# proto_shield_MEGA-REV3.net
KiCad netlist of a schematic drawn in EAGLE
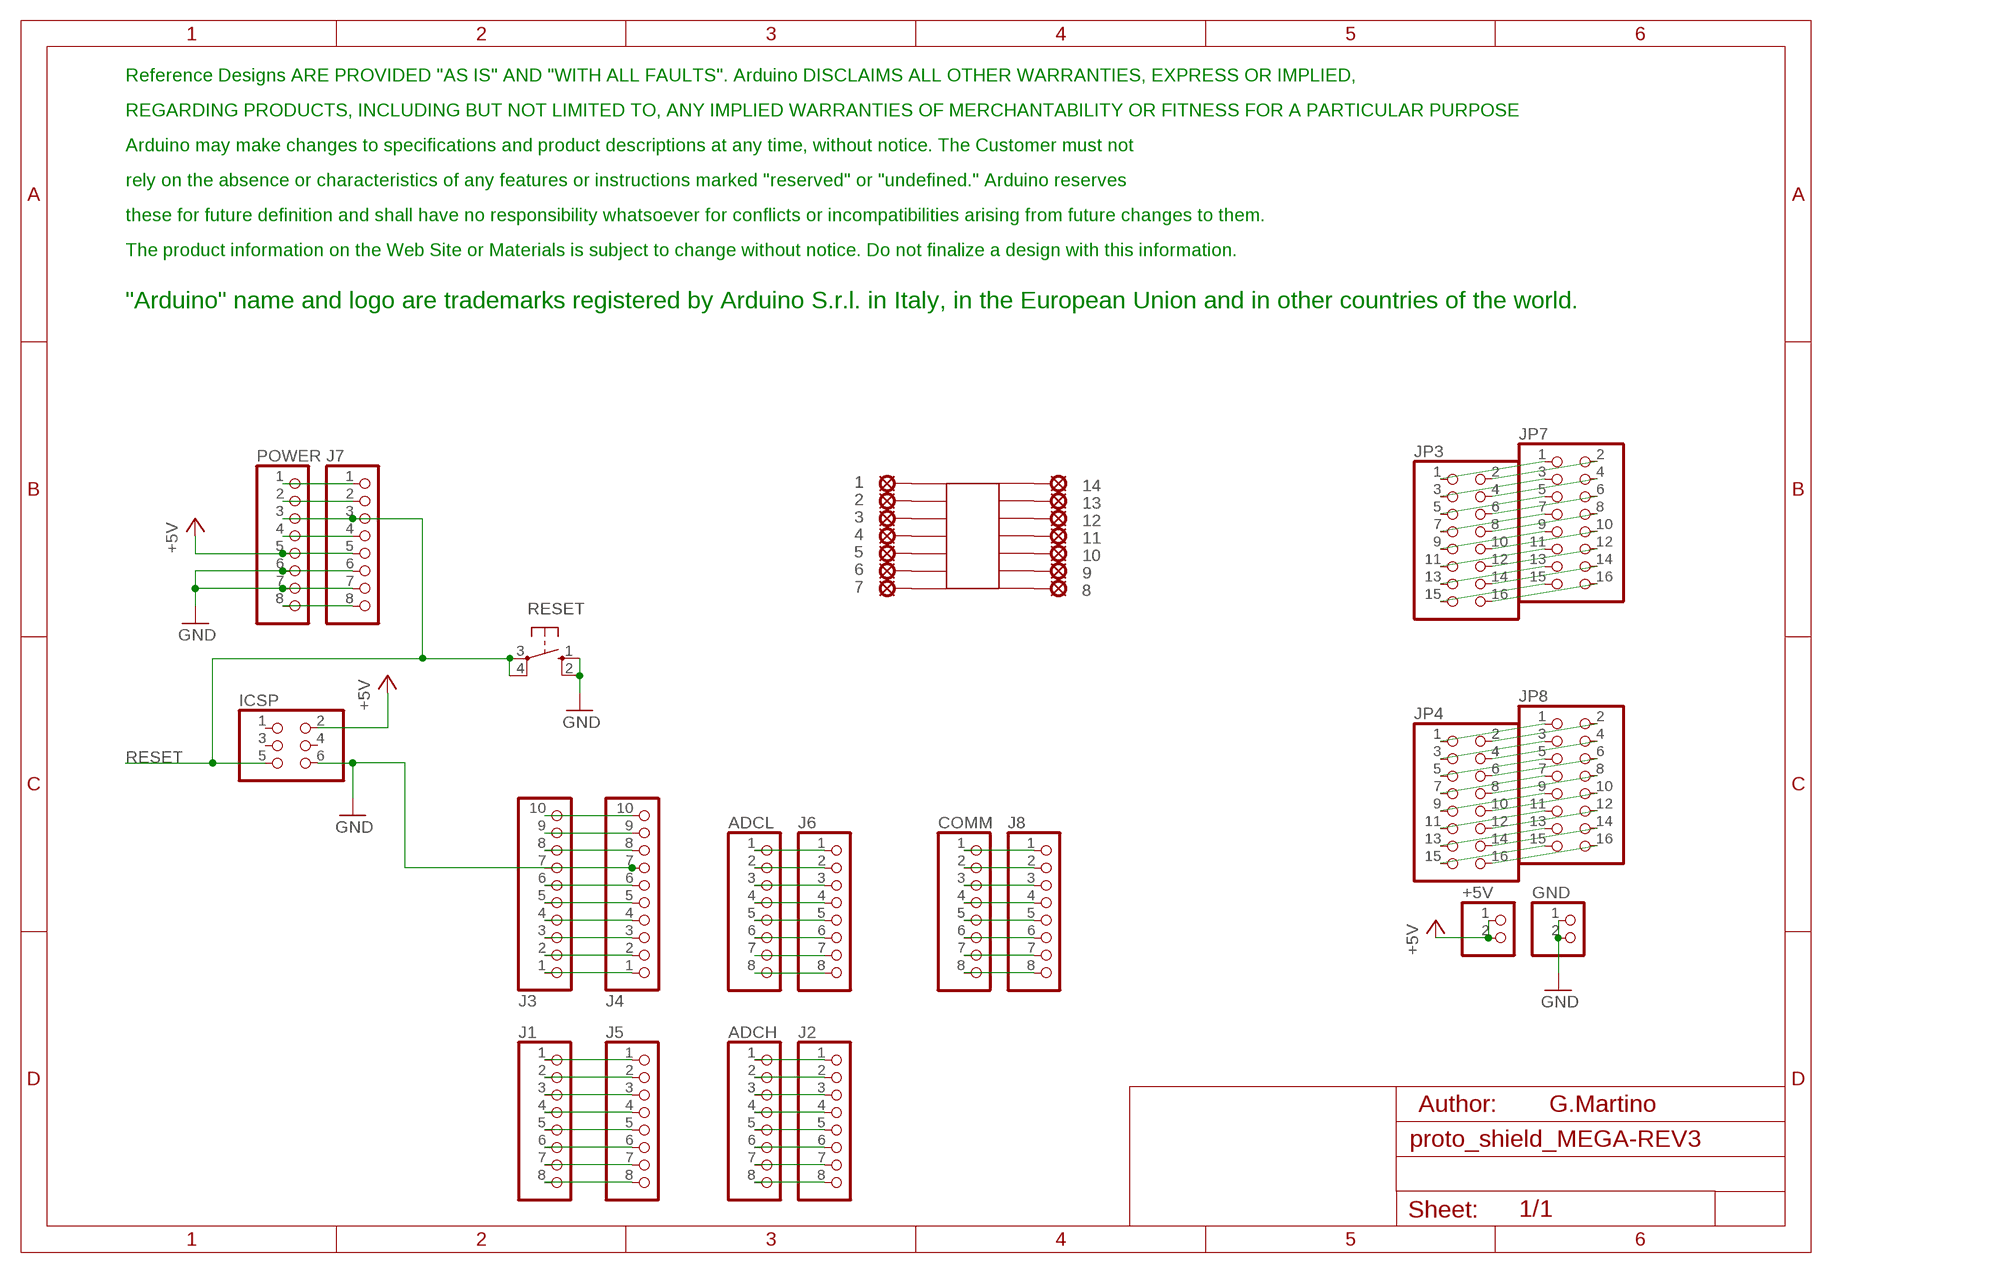
[diagram p0: schematic, sheet 1]

(export (version "E")
  (design (tool "Eeschema 10.0.6"))
  (components
    (comp (ref "+5V")
      (value "PINHD-1X2")
      (footprint "eagle-import:1X02")
      (libsource (lib "eagle-import") (part "PINHD-1X2"))
    )
    (comp (ref "1")
      (value "LSP10")
      (footprint "eagle-import:LSP10")
      (libsource (lib "eagle-import") (part "LSP10"))
    )
    (comp (ref "2")
      (value "LSP10")
      (footprint "eagle-import:LSP10")
      (libsource (lib "eagle-import") (part "LSP10"))
    )
    (comp (ref "3")
      (value "LSP10")
      (footprint "eagle-import:LSP10")
      (libsource (lib "eagle-import") (part "LSP10"))
    )
    (comp (ref "4")
      (value "LSP10")
      (footprint "eagle-import:LSP10")
      (libsource (lib "eagle-import") (part "LSP10"))
    )
    (comp (ref "5")
      (value "LSP10")
      (footprint "eagle-import:LSP10")
      (libsource (lib "eagle-import") (part "LSP10"))
    )
    (comp (ref "6")
      (value "LSP10")
      (footprint "eagle-import:LSP10")
      (libsource (lib "eagle-import") (part "LSP10"))
    )
    (comp (ref "7")
      (value "LSP10")
      (footprint "eagle-import:LSP10")
      (libsource (lib "eagle-import") (part "LSP10"))
    )
    (comp (ref "8")
      (value "LSP10")
      (footprint "eagle-import:LSP10")
      (libsource (lib "eagle-import") (part "LSP10"))
    )
    (comp (ref "9")
      (value "LSP10")
      (footprint "eagle-import:LSP10")
      (libsource (lib "eagle-import") (part "LSP10"))
    )
    (comp (ref "10")
      (value "LSP10")
      (footprint "eagle-import:LSP10")
      (libsource (lib "eagle-import") (part "LSP10"))
    )
    (comp (ref "11")
      (value "LSP10")
      (footprint "eagle-import:LSP10")
      (libsource (lib "eagle-import") (part "LSP10"))
    )
    (comp (ref "12")
      (value "LSP10")
      (footprint "eagle-import:LSP10")
      (libsource (lib "eagle-import") (part "LSP10"))
    )
    (comp (ref "13")
      (value "LSP10")
      (footprint "eagle-import:LSP10")
      (libsource (lib "eagle-import") (part "LSP10"))
    )
    (comp (ref "14")
      (value "LSP10")
      (footprint "eagle-import:LSP10")
      (libsource (lib "eagle-import") (part "LSP10"))
    )
    (comp (ref "ADCH")
      (value "PINHD-1X8TH")
      (footprint "eagle-import:1X08-TH")
      (libsource (lib "eagle-import") (part "PINHD-1X8TH"))
    )
    (comp (ref "ADCL")
      (value "PINHD-1X8TH")
      (footprint "eagle-import:1X08-TH")
      (libsource (lib "eagle-import") (part "PINHD-1X8TH"))
    )
    (comp (ref "COMM")
      (value "PINHD-1X8TH")
      (footprint "eagle-import:1X08-TH")
      (libsource (lib "eagle-import") (part "PINHD-1X8TH"))
    )
    (comp (ref "GND")
      (value "PINHD-1X2")
      (footprint "eagle-import:1X02")
      (libsource (lib "eagle-import") (part "PINHD-1X2"))
    )
    (comp (ref "IC2")
      (value "SMD-14")
      (footprint "eagle-import:SO-14NMW")
      (libsource (lib "eagle-import") (part "SMD-14"))
    )
    (comp (ref "ICSP")
      (value "PINHD-2X3")
      (footprint "eagle-import:2X03")
      (libsource (lib "eagle-import") (part "PINHD-2X3"))
    )
    (comp (ref "J1")
      (value "PINHD-1X8TH")
      (footprint "eagle-import:1X08-TH")
      (libsource (lib "eagle-import") (part "PINHD-1X8TH"))
    )
    (comp (ref "J2")
      (value "PINHD-1X8TH")
      (footprint "eagle-import:1X08-TH")
      (libsource (lib "eagle-import") (part "PINHD-1X8TH"))
    )
    (comp (ref "J3")
      (value "PINHD-1X10TH")
      (footprint "eagle-import:1X10-TH")
      (libsource (lib "eagle-import") (part "PINHD-1X10TH"))
    )
    (comp (ref "J4")
      (value "PINHD-1X10TH")
      (footprint "eagle-import:1X10-TH")
      (libsource (lib "eagle-import") (part "PINHD-1X10TH"))
    )
    (comp (ref "J5")
      (value "PINHD-1X8TH")
      (footprint "eagle-import:1X08-TH")
      (libsource (lib "eagle-import") (part "PINHD-1X8TH"))
    )
    (comp (ref "J6")
      (value "PINHD-1X8TH")
      (footprint "eagle-import:1X08-TH")
      (libsource (lib "eagle-import") (part "PINHD-1X8TH"))
    )
    (comp (ref "J7")
      (value "PINHD-1X8TH")
      (footprint "eagle-import:1X08-TH")
      (libsource (lib "eagle-import") (part "PINHD-1X8TH"))
    )
    (comp (ref "J8")
      (value "PINHD-1X8TH")
      (footprint "eagle-import:1X08-TH")
      (libsource (lib "eagle-import") (part "PINHD-1X8TH"))
    )
    (comp (ref "JP3")
      (value "PINHD-2X8")
      (footprint "eagle-import:2X08")
      (libsource (lib "eagle-import") (part "PINHD-2X8"))
    )
    (comp (ref "JP4")
      (value "PINHD-2X8")
      (footprint "eagle-import:2X08")
      (libsource (lib "eagle-import") (part "PINHD-2X8"))
    )
    (comp (ref "JP7")
      (value "PINHD-2X8")
      (footprint "eagle-import:2X08")
      (libsource (lib "eagle-import") (part "PINHD-2X8"))
    )
    (comp (ref "JP8")
      (value "PINHD-2X8")
      (footprint "eagle-import:2X08")
      (libsource (lib "eagle-import") (part "PINHD-2X8"))
    )
    (comp (ref "POWER")
      (value "PINHD-1X8TH")
      (footprint "eagle-import:1X08-TH")
      (libsource (lib "eagle-import") (part "PINHD-1X8TH"))
    )
    (comp (ref "RESET")
      (value "10-XX")
      (footprint "eagle-import:B3F-10XX")
      (libsource (lib "eagle-import") (part "10-XX"))
    )
    (comp (ref "U$1")
      (value "DISCLAIMER_MINI")
      (footprint "eagle-import:DISCLAIMER")
      (libsource (lib "eagle-import") (part "DISCLAIMER_MINI"))
    )
  )
  (nets
    (net (code "1") (name "+5V") (class "Default")
      (node (ref "+5V") (pin "1") (pinfunction "1_1") (pintype "passive"))
      (node (ref "+5V") (pin "2") (pinfunction "2_2") (pintype "passive"))
      (node (ref "ICSP") (pin "2") (pinfunction "2_2") (pintype "passive"))
      (node (ref "J7") (pin "5") (pinfunction "5_5") (pintype "passive"))
      (node (ref "POWER") (pin "5") (pinfunction "5_5") (pintype "passive"))
    )
    (net (code "2") (name "/RESET") (class "Default")
      (node (ref "ICSP") (pin "5") (pinfunction "5_5") (pintype "passive"))
      (node (ref "J7") (pin "3") (pinfunction "3_3") (pintype "passive"))
      (node (ref "POWER") (pin "3") (pinfunction "3_3") (pintype "passive"))
      (node (ref "RESET") (pin "3") (pinfunction "P_3") (pintype "passive"))
      (node (ref "RESET") (pin "4") (pinfunction "P1_4") (pintype "passive"))
    )
    (net (code "3") (name "GND") (class "Default")
      (node (ref "GND") (pin "1") (pinfunction "1_1") (pintype "passive"))
      (node (ref "GND") (pin "2") (pinfunction "2_2") (pintype "passive"))
      (node (ref "ICSP") (pin "6") (pinfunction "6_6") (pintype "passive"))
      (node (ref "J3") (pin "7") (pinfunction "7_7") (pintype "passive"))
      (node (ref "J4") (pin "7") (pinfunction "7_7") (pintype "passive"))
      (node (ref "J7") (pin "6") (pinfunction "6_6") (pintype "passive"))
      (node (ref "J7") (pin "7") (pinfunction "7_7") (pintype "passive"))
      (node (ref "POWER") (pin "6") (pinfunction "6_6") (pintype "passive"))
      (node (ref "POWER") (pin "7") (pinfunction "7_7") (pintype "passive"))
      (node (ref "RESET") (pin "1") (pinfunction "S_1") (pintype "passive"))
      (node (ref "RESET") (pin "2") (pinfunction "S1_2") (pintype "passive"))
    )
    (net (code "4") (name "Net-(1-PadMP)") (class "Default")
      (node (ref "1") (pin "MP") (pinfunction "MP_MP") (pintype "passive"))
      (node (ref "IC2") (pin "P$1") (pinfunction "P$1_P$1") (pintype "bidirectional"))
    )
    (net (code "5") (name "Net-(2-PadMP)") (class "Default")
      (node (ref "2") (pin "MP") (pinfunction "MP_MP") (pintype "passive"))
      (node (ref "IC2") (pin "P$2") (pinfunction "P$2_P$2") (pintype "bidirectional"))
    )
    (net (code "6") (name "Net-(3-PadMP)") (class "Default")
      (node (ref "3") (pin "MP") (pinfunction "MP_MP") (pintype "passive"))
      (node (ref "IC2") (pin "P$3") (pinfunction "P$3_P$3") (pintype "bidirectional"))
    )
    (net (code "7") (name "Net-(4-PadMP)") (class "Default")
      (node (ref "4") (pin "MP") (pinfunction "MP_MP") (pintype "passive"))
      (node (ref "IC2") (pin "P$4") (pinfunction "P$4_P$4") (pintype "bidirectional"))
    )
    (net (code "8") (name "Net-(5-PadMP)") (class "Default")
      (node (ref "5") (pin "MP") (pinfunction "MP_MP") (pintype "passive"))
      (node (ref "IC2") (pin "P$5") (pinfunction "P$5_P$5") (pintype "bidirectional"))
    )
    (net (code "9") (name "Net-(6-PadMP)") (class "Default")
      (node (ref "6") (pin "MP") (pinfunction "MP_MP") (pintype "passive"))
      (node (ref "IC2") (pin "P$6") (pinfunction "P$6_P$6") (pintype "bidirectional"))
    )
    (net (code "10") (name "Net-(7-PadMP)") (class "Default")
      (node (ref "7") (pin "MP") (pinfunction "MP_MP") (pintype "passive"))
      (node (ref "IC2") (pin "P$7") (pinfunction "P$7_P$7") (pintype "bidirectional"))
    )
    (net (code "11") (name "Net-(8-PadMP)") (class "Default")
      (node (ref "8") (pin "MP") (pinfunction "MP_MP") (pintype "passive"))
      (node (ref "IC2") (pin "P$8") (pinfunction "P$8_P$8") (pintype "bidirectional"))
    )
    (net (code "12") (name "Net-(9-PadMP)") (class "Default")
      (node (ref "9") (pin "MP") (pinfunction "MP_MP") (pintype "passive"))
      (node (ref "IC2") (pin "P$9") (pinfunction "P$9_P$9") (pintype "bidirectional"))
    )
    (net (code "13") (name "Net-(10-PadMP)") (class "Default")
      (node (ref "10") (pin "MP") (pinfunction "MP_MP") (pintype "passive"))
      (node (ref "IC2") (pin "P$10") (pinfunction "P$10_P$10") (pintype "bidirectional"))
    )
    (net (code "14") (name "Net-(11-PadMP)") (class "Default")
      (node (ref "11") (pin "MP") (pinfunction "MP_MP") (pintype "passive"))
      (node (ref "IC2") (pin "P$11") (pinfunction "P$11_P$11") (pintype "bidirectional"))
    )
    (net (code "15") (name "Net-(12-PadMP)") (class "Default")
      (node (ref "12") (pin "MP") (pinfunction "MP_MP") (pintype "passive"))
      (node (ref "IC2") (pin "P$12") (pinfunction "P$12_P$12") (pintype "bidirectional"))
    )
    (net (code "16") (name "Net-(13-PadMP)") (class "Default")
      (node (ref "13") (pin "MP") (pinfunction "MP_MP") (pintype "passive"))
      (node (ref "IC2") (pin "P$13") (pinfunction "P$13_P$13") (pintype "bidirectional"))
    )
    (net (code "17") (name "Net-(14-PadMP)") (class "Default")
      (node (ref "14") (pin "MP") (pinfunction "MP_MP") (pintype "passive"))
      (node (ref "IC2") (pin "P$14") (pinfunction "P$14_P$14") (pintype "bidirectional"))
    )
    (net (code "18") (name "Net-(ADCH-Pad1)") (class "Default")
      (node (ref "ADCH") (pin "1") (pinfunction "1_1") (pintype "passive"))
      (node (ref "J2") (pin "1") (pinfunction "1_1") (pintype "passive"))
    )
    (net (code "19") (name "Net-(ADCH-Pad2)") (class "Default")
      (node (ref "ADCH") (pin "2") (pinfunction "2_2") (pintype "passive"))
      (node (ref "J2") (pin "2") (pinfunction "2_2") (pintype "passive"))
    )
    (net (code "20") (name "Net-(ADCH-Pad3)") (class "Default")
      (node (ref "ADCH") (pin "3") (pinfunction "3_3") (pintype "passive"))
      (node (ref "J2") (pin "3") (pinfunction "3_3") (pintype "passive"))
    )
    (net (code "21") (name "Net-(ADCH-Pad4)") (class "Default")
      (node (ref "ADCH") (pin "4") (pinfunction "4_4") (pintype "passive"))
      (node (ref "J2") (pin "4") (pinfunction "4_4") (pintype "passive"))
    )
    (net (code "22") (name "Net-(ADCH-Pad5)") (class "Default")
      (node (ref "ADCH") (pin "5") (pinfunction "5_5") (pintype "passive"))
      (node (ref "J2") (pin "5") (pinfunction "5_5") (pintype "passive"))
    )
    (net (code "23") (name "Net-(ADCH-Pad6)") (class "Default")
      (node (ref "ADCH") (pin "6") (pinfunction "6_6") (pintype "passive"))
      (node (ref "J2") (pin "6") (pinfunction "6_6") (pintype "passive"))
    )
    (net (code "24") (name "Net-(ADCH-Pad7)") (class "Default")
      (node (ref "ADCH") (pin "7") (pinfunction "7_7") (pintype "passive"))
      (node (ref "J2") (pin "7") (pinfunction "7_7") (pintype "passive"))
    )
    (net (code "25") (name "Net-(ADCH-Pad8)") (class "Default")
      (node (ref "ADCH") (pin "8") (pinfunction "8_8") (pintype "passive"))
      (node (ref "J2") (pin "8") (pinfunction "8_8") (pintype "passive"))
    )
    (net (code "26") (name "Net-(ADCL-Pad1)") (class "Default")
      (node (ref "ADCL") (pin "1") (pinfunction "1_1") (pintype "passive"))
      (node (ref "J6") (pin "1") (pinfunction "1_1") (pintype "passive"))
    )
    (net (code "27") (name "Net-(ADCL-Pad2)") (class "Default")
      (node (ref "ADCL") (pin "2") (pinfunction "2_2") (pintype "passive"))
      (node (ref "J6") (pin "2") (pinfunction "2_2") (pintype "passive"))
    )
    (net (code "28") (name "Net-(ADCL-Pad3)") (class "Default")
      (node (ref "ADCL") (pin "3") (pinfunction "3_3") (pintype "passive"))
      (node (ref "J6") (pin "3") (pinfunction "3_3") (pintype "passive"))
    )
    (net (code "29") (name "Net-(ADCL-Pad4)") (class "Default")
      (node (ref "ADCL") (pin "4") (pinfunction "4_4") (pintype "passive"))
      (node (ref "J6") (pin "4") (pinfunction "4_4") (pintype "passive"))
    )
    (net (code "30") (name "Net-(ADCL-Pad5)") (class "Default")
      (node (ref "ADCL") (pin "5") (pinfunction "5_5") (pintype "passive"))
      (node (ref "J6") (pin "5") (pinfunction "5_5") (pintype "passive"))
    )
    (net (code "31") (name "Net-(ADCL-Pad6)") (class "Default")
      (node (ref "ADCL") (pin "6") (pinfunction "6_6") (pintype "passive"))
      (node (ref "J6") (pin "6") (pinfunction "6_6") (pintype "passive"))
    )
    (net (code "32") (name "Net-(ADCL-Pad7)") (class "Default")
      (node (ref "ADCL") (pin "7") (pinfunction "7_7") (pintype "passive"))
      (node (ref "J6") (pin "7") (pinfunction "7_7") (pintype "passive"))
    )
    (net (code "33") (name "Net-(ADCL-Pad8)") (class "Default")
      (node (ref "ADCL") (pin "8") (pinfunction "8_8") (pintype "passive"))
      (node (ref "J6") (pin "8") (pinfunction "8_8") (pintype "passive"))
    )
    (net (code "34") (name "Net-(COMM-Pad1)") (class "Default")
      (node (ref "COMM") (pin "1") (pinfunction "1_1") (pintype "passive"))
      (node (ref "J8") (pin "1") (pinfunction "1_1") (pintype "passive"))
    )
    (net (code "35") (name "Net-(COMM-Pad2)") (class "Default")
      (node (ref "COMM") (pin "2") (pinfunction "2_2") (pintype "passive"))
      (node (ref "J8") (pin "2") (pinfunction "2_2") (pintype "passive"))
    )
    (net (code "36") (name "Net-(COMM-Pad3)") (class "Default")
      (node (ref "COMM") (pin "3") (pinfunction "3_3") (pintype "passive"))
      (node (ref "J8") (pin "3") (pinfunction "3_3") (pintype "passive"))
    )
    (net (code "37") (name "Net-(COMM-Pad4)") (class "Default")
      (node (ref "COMM") (pin "4") (pinfunction "4_4") (pintype "passive"))
      (node (ref "J8") (pin "4") (pinfunction "4_4") (pintype "passive"))
    )
    (net (code "38") (name "Net-(COMM-Pad5)") (class "Default")
      (node (ref "COMM") (pin "5") (pinfunction "5_5") (pintype "passive"))
      (node (ref "J8") (pin "5") (pinfunction "5_5") (pintype "passive"))
    )
    (net (code "39") (name "Net-(COMM-Pad6)") (class "Default")
      (node (ref "COMM") (pin "6") (pinfunction "6_6") (pintype "passive"))
      (node (ref "J8") (pin "6") (pinfunction "6_6") (pintype "passive"))
    )
    (net (code "40") (name "Net-(COMM-Pad7)") (class "Default")
      (node (ref "COMM") (pin "7") (pinfunction "7_7") (pintype "passive"))
      (node (ref "J8") (pin "7") (pinfunction "7_7") (pintype "passive"))
    )
    (net (code "41") (name "Net-(COMM-Pad8)") (class "Default")
      (node (ref "COMM") (pin "8") (pinfunction "8_8") (pintype "passive"))
      (node (ref "J8") (pin "8") (pinfunction "8_8") (pintype "passive"))
    )
    (net (code "42") (name "Net-(J1-Pad1)") (class "Default")
      (node (ref "J1") (pin "1") (pinfunction "1_1") (pintype "passive"))
      (node (ref "J5") (pin "1") (pinfunction "1_1") (pintype "passive"))
    )
    (net (code "43") (name "Net-(J1-Pad2)") (class "Default")
      (node (ref "J1") (pin "2") (pinfunction "2_2") (pintype "passive"))
      (node (ref "J5") (pin "2") (pinfunction "2_2") (pintype "passive"))
    )
    (net (code "44") (name "Net-(J1-Pad3)") (class "Default")
      (node (ref "J1") (pin "3") (pinfunction "3_3") (pintype "passive"))
      (node (ref "J5") (pin "3") (pinfunction "3_3") (pintype "passive"))
    )
    (net (code "45") (name "Net-(J1-Pad4)") (class "Default")
      (node (ref "J1") (pin "4") (pinfunction "4_4") (pintype "passive"))
      (node (ref "J5") (pin "4") (pinfunction "4_4") (pintype "passive"))
    )
    (net (code "46") (name "Net-(J1-Pad5)") (class "Default")
      (node (ref "J1") (pin "5") (pinfunction "5_5") (pintype "passive"))
      (node (ref "J5") (pin "5") (pinfunction "5_5") (pintype "passive"))
    )
    (net (code "47") (name "Net-(J1-Pad6)") (class "Default")
      (node (ref "J1") (pin "6") (pinfunction "6_6") (pintype "passive"))
      (node (ref "J5") (pin "6") (pinfunction "6_6") (pintype "passive"))
    )
    (net (code "48") (name "Net-(J1-Pad7)") (class "Default")
      (node (ref "J1") (pin "7") (pinfunction "7_7") (pintype "passive"))
      (node (ref "J5") (pin "7") (pinfunction "7_7") (pintype "passive"))
    )
    (net (code "49") (name "Net-(J1-Pad8)") (class "Default")
      (node (ref "J1") (pin "8") (pinfunction "8_8") (pintype "passive"))
      (node (ref "J5") (pin "8") (pinfunction "8_8") (pintype "passive"))
    )
    (net (code "50") (name "Net-(J3-Pad1)") (class "Default")
      (node (ref "J3") (pin "1") (pinfunction "1_1") (pintype "passive"))
      (node (ref "J4") (pin "1") (pinfunction "1_1") (pintype "passive"))
    )
    (net (code "51") (name "Net-(J3-Pad2)") (class "Default")
      (node (ref "J3") (pin "2") (pinfunction "2_2") (pintype "passive"))
      (node (ref "J4") (pin "2") (pinfunction "2_2") (pintype "passive"))
    )
    (net (code "52") (name "Net-(J3-Pad3)") (class "Default")
      (node (ref "J3") (pin "3") (pinfunction "3_3") (pintype "passive"))
      (node (ref "J4") (pin "3") (pinfunction "3_3") (pintype "passive"))
    )
    (net (code "53") (name "Net-(J3-Pad4)") (class "Default")
      (node (ref "J3") (pin "4") (pinfunction "4_4") (pintype "passive"))
      (node (ref "J4") (pin "4") (pinfunction "4_4") (pintype "passive"))
    )
    (net (code "54") (name "Net-(J3-Pad5)") (class "Default")
      (node (ref "J3") (pin "5") (pinfunction "5_5") (pintype "passive"))
      (node (ref "J4") (pin "5") (pinfunction "5_5") (pintype "passive"))
    )
    (net (code "55") (name "Net-(J3-Pad6)") (class "Default")
      (node (ref "J3") (pin "6") (pinfunction "6_6") (pintype "passive"))
      (node (ref "J4") (pin "6") (pinfunction "6_6") (pintype "passive"))
    )
    (net (code "56") (name "Net-(J3-Pad8)") (class "Default")
      (node (ref "J3") (pin "8") (pinfunction "8_8") (pintype "passive"))
      (node (ref "J4") (pin "8") (pinfunction "8_8") (pintype "passive"))
    )
    (net (code "57") (name "Net-(J3-Pad9)") (class "Default")
      (node (ref "J3") (pin "9") (pinfunction "9_9") (pintype "passive"))
      (node (ref "J4") (pin "9") (pinfunction "9_9") (pintype "passive"))
    )
    (net (code "58") (name "Net-(J3-Pad10)") (class "Default")
      (node (ref "J3") (pin "10") (pinfunction "10_10") (pintype "passive"))
      (node (ref "J4") (pin "10") (pinfunction "10_10") (pintype "passive"))
    )
    (net (code "59") (name "Net-(J7-Pad1)") (class "Default")
      (node (ref "J7") (pin "1") (pinfunction "1_1") (pintype "passive"))
      (node (ref "POWER") (pin "1") (pinfunction "1_1") (pintype "passive"))
    )
    (net (code "60") (name "Net-(J7-Pad2)") (class "Default")
      (node (ref "J7") (pin "2") (pinfunction "2_2") (pintype "passive"))
      (node (ref "POWER") (pin "2") (pinfunction "2_2") (pintype "passive"))
    )
    (net (code "61") (name "Net-(J7-Pad4)") (class "Default")
      (node (ref "J7") (pin "4") (pinfunction "4_4") (pintype "passive"))
      (node (ref "POWER") (pin "4") (pinfunction "4_4") (pintype "passive"))
    )
    (net (code "62") (name "Net-(J7-Pad8)") (class "Default")
      (node (ref "J7") (pin "8") (pinfunction "8_8") (pintype "passive"))
      (node (ref "POWER") (pin "8") (pinfunction "8_8") (pintype "passive"))
    )
    (net (code "63") (name "Net-(JP3-Pad1)") (class "Default")
      (node (ref "JP3") (pin "1") (pinfunction "1_1") (pintype "passive"))
      (node (ref "JP7") (pin "1") (pinfunction "1_1") (pintype "passive"))
    )
    (net (code "64") (name "Net-(JP3-Pad2)") (class "Default")
      (node (ref "JP3") (pin "2") (pinfunction "2_2") (pintype "passive"))
      (node (ref "JP7") (pin "2") (pinfunction "2_2") (pintype "passive"))
    )
    (net (code "65") (name "Net-(JP3-Pad3)") (class "Default")
      (node (ref "JP3") (pin "3") (pinfunction "3_3") (pintype "passive"))
      (node (ref "JP7") (pin "3") (pinfunction "3_3") (pintype "passive"))
    )
    (net (code "66") (name "Net-(JP3-Pad4)") (class "Default")
      (node (ref "JP3") (pin "4") (pinfunction "4_4") (pintype "passive"))
      (node (ref "JP7") (pin "4") (pinfunction "4_4") (pintype "passive"))
    )
    (net (code "67") (name "Net-(JP3-Pad5)") (class "Default")
      (node (ref "JP3") (pin "5") (pinfunction "5_5") (pintype "passive"))
      (node (ref "JP7") (pin "5") (pinfunction "5_5") (pintype "passive"))
    )
    (net (code "68") (name "Net-(JP3-Pad6)") (class "Default")
      (node (ref "JP3") (pin "6") (pinfunction "6_6") (pintype "passive"))
      (node (ref "JP7") (pin "6") (pinfunction "6_6") (pintype "passive"))
    )
    (net (code "69") (name "Net-(JP3-Pad7)") (class "Default")
      (node (ref "JP3") (pin "7") (pinfunction "7_7") (pintype "passive"))
      (node (ref "JP7") (pin "7") (pinfunction "7_7") (pintype "passive"))
    )
    (net (code "70") (name "Net-(JP3-Pad8)") (class "Default")
      (node (ref "JP3") (pin "8") (pinfunction "8_8") (pintype "passive"))
      (node (ref "JP7") (pin "8") (pinfunction "8_8") (pintype "passive"))
    )
    (net (code "71") (name "Net-(JP3-Pad9)") (class "Default")
      (node (ref "JP3") (pin "9") (pinfunction "9_9") (pintype "passive"))
      (node (ref "JP7") (pin "9") (pinfunction "9_9") (pintype "passive"))
    )
    (net (code "72") (name "Net-(JP3-Pad10)") (class "Default")
      (node (ref "JP3") (pin "10") (pinfunction "10_10") (pintype "passive"))
      (node (ref "JP7") (pin "10") (pinfunction "10_10") (pintype "passive"))
    )
    (net (code "73") (name "Net-(JP3-Pad11)") (class "Default")
      (node (ref "JP3") (pin "11") (pinfunction "11_11") (pintype "passive"))
      (node (ref "JP7") (pin "11") (pinfunction "11_11") (pintype "passive"))
    )
    (net (code "74") (name "Net-(JP3-Pad12)") (class "Default")
      (node (ref "JP3") (pin "12") (pinfunction "12_12") (pintype "passive"))
      (node (ref "JP7") (pin "12") (pinfunction "12_12") (pintype "passive"))
    )
    (net (code "75") (name "Net-(JP3-Pad13)") (class "Default")
      (node (ref "JP3") (pin "13") (pinfunction "13_13") (pintype "passive"))
      (node (ref "JP7") (pin "13") (pinfunction "13_13") (pintype "passive"))
    )
    (net (code "76") (name "Net-(JP3-Pad14)") (class "Default")
      (node (ref "JP3") (pin "14") (pinfunction "14_14") (pintype "passive"))
      (node (ref "JP7") (pin "14") (pinfunction "14_14") (pintype "passive"))
    )
    (net (code "77") (name "Net-(JP3-Pad15)") (class "Default")
      (node (ref "JP3") (pin "15") (pinfunction "15_15") (pintype "passive"))
      (node (ref "JP7") (pin "15") (pinfunction "15_15") (pintype "passive"))
    )
    (net (code "78") (name "Net-(JP3-Pad16)") (class "Default")
      (node (ref "JP3") (pin "16") (pinfunction "16_16") (pintype "passive"))
      (node (ref "JP7") (pin "16") (pinfunction "16_16") (pintype "passive"))
    )
    (net (code "79") (name "Net-(JP4-Pad1)") (class "Default")
      (node (ref "JP4") (pin "1") (pinfunction "1_1") (pintype "passive"))
      (node (ref "JP8") (pin "1") (pinfunction "1_1") (pintype "passive"))
    )
    (net (code "80") (name "Net-(JP4-Pad2)") (class "Default")
      (node (ref "JP4") (pin "2") (pinfunction "2_2") (pintype "passive"))
      (node (ref "JP8") (pin "2") (pinfunction "2_2") (pintype "passive"))
    )
    (net (code "81") (name "Net-(JP4-Pad3)") (class "Default")
      (node (ref "JP4") (pin "3") (pinfunction "3_3") (pintype "passive"))
      (node (ref "JP8") (pin "3") (pinfunction "3_3") (pintype "passive"))
    )
    (net (code "82") (name "Net-(JP4-Pad4)") (class "Default")
      (node (ref "JP4") (pin "4") (pinfunction "4_4") (pintype "passive"))
      (node (ref "JP8") (pin "4") (pinfunction "4_4") (pintype "passive"))
    )
    (net (code "83") (name "Net-(JP4-Pad5)") (class "Default")
      (node (ref "JP4") (pin "5") (pinfunction "5_5") (pintype "passive"))
      (node (ref "JP8") (pin "5") (pinfunction "5_5") (pintype "passive"))
    )
    (net (code "84") (name "Net-(JP4-Pad6)") (class "Default")
      (node (ref "JP4") (pin "6") (pinfunction "6_6") (pintype "passive"))
      (node (ref "JP8") (pin "6") (pinfunction "6_6") (pintype "passive"))
    )
    (net (code "85") (name "Net-(JP4-Pad7)") (class "Default")
      (node (ref "JP4") (pin "7") (pinfunction "7_7") (pintype "passive"))
      (node (ref "JP8") (pin "7") (pinfunction "7_7") (pintype "passive"))
    )
    (net (code "86") (name "Net-(JP4-Pad8)") (class "Default")
      (node (ref "JP4") (pin "8") (pinfunction "8_8") (pintype "passive"))
      (node (ref "JP8") (pin "8") (pinfunction "8_8") (pintype "passive"))
    )
    (net (code "87") (name "Net-(JP4-Pad9)") (class "Default")
      (node (ref "JP4") (pin "9") (pinfunction "9_9") (pintype "passive"))
      (node (ref "JP8") (pin "9") (pinfunction "9_9") (pintype "passive"))
    )
    (net (code "88") (name "Net-(JP4-Pad10)") (class "Default")
      (node (ref "JP4") (pin "10") (pinfunction "10_10") (pintype "passive"))
      (node (ref "JP8") (pin "10") (pinfunction "10_10") (pintype "passive"))
    )
    (net (code "89") (name "Net-(JP4-Pad11)") (class "Default")
      (node (ref "JP4") (pin "11") (pinfunction "11_11") (pintype "passive"))
      (node (ref "JP8") (pin "11") (pinfunction "11_11") (pintype "passive"))
    )
    (net (code "90") (name "Net-(JP4-Pad12)") (class "Default")
      (node (ref "JP4") (pin "12") (pinfunction "12_12") (pintype "passive"))
      (node (ref "JP8") (pin "12") (pinfunction "12_12") (pintype "passive"))
    )
    (net (code "91") (name "Net-(JP4-Pad13)") (class "Default")
      (node (ref "JP4") (pin "13") (pinfunction "13_13") (pintype "passive"))
      (node (ref "JP8") (pin "13") (pinfunction "13_13") (pintype "passive"))
    )
    (net (code "92") (name "Net-(JP4-Pad14)") (class "Default")
      (node (ref "JP4") (pin "14") (pinfunction "14_14") (pintype "passive"))
      (node (ref "JP8") (pin "14") (pinfunction "14_14") (pintype "passive"))
    )
    (net (code "93") (name "Net-(JP4-Pad15)") (class "Default")
      (node (ref "JP4") (pin "15") (pinfunction "15_15") (pintype "passive"))
      (node (ref "JP8") (pin "15") (pinfunction "15_15") (pintype "passive"))
    )
    (net (code "94") (name "Net-(JP4-Pad16)") (class "Default")
      (node (ref "JP4") (pin "16") (pinfunction "16_16") (pintype "passive"))
      (node (ref "JP8") (pin "16") (pinfunction "16_16") (pintype "passive"))
    )
    (net (code "95") (name "unconnected-(ICSP-Pad1)") (class "Default")
      (node (ref "ICSP") (pin "1") (pinfunction "1_1") (pintype "passive"))
    )
    (net (code "96") (name "unconnected-(ICSP-Pad3)") (class "Default")
      (node (ref "ICSP") (pin "3") (pinfunction "3_3") (pintype "passive"))
    )
    (net (code "97") (name "unconnected-(ICSP-Pad4)") (class "Default")
      (node (ref "ICSP") (pin "4") (pinfunction "4_4") (pintype "passive"))
    )
  )
)
